# NumberMagic.net
KiCad netlist of a schematic drawn in EAGLE
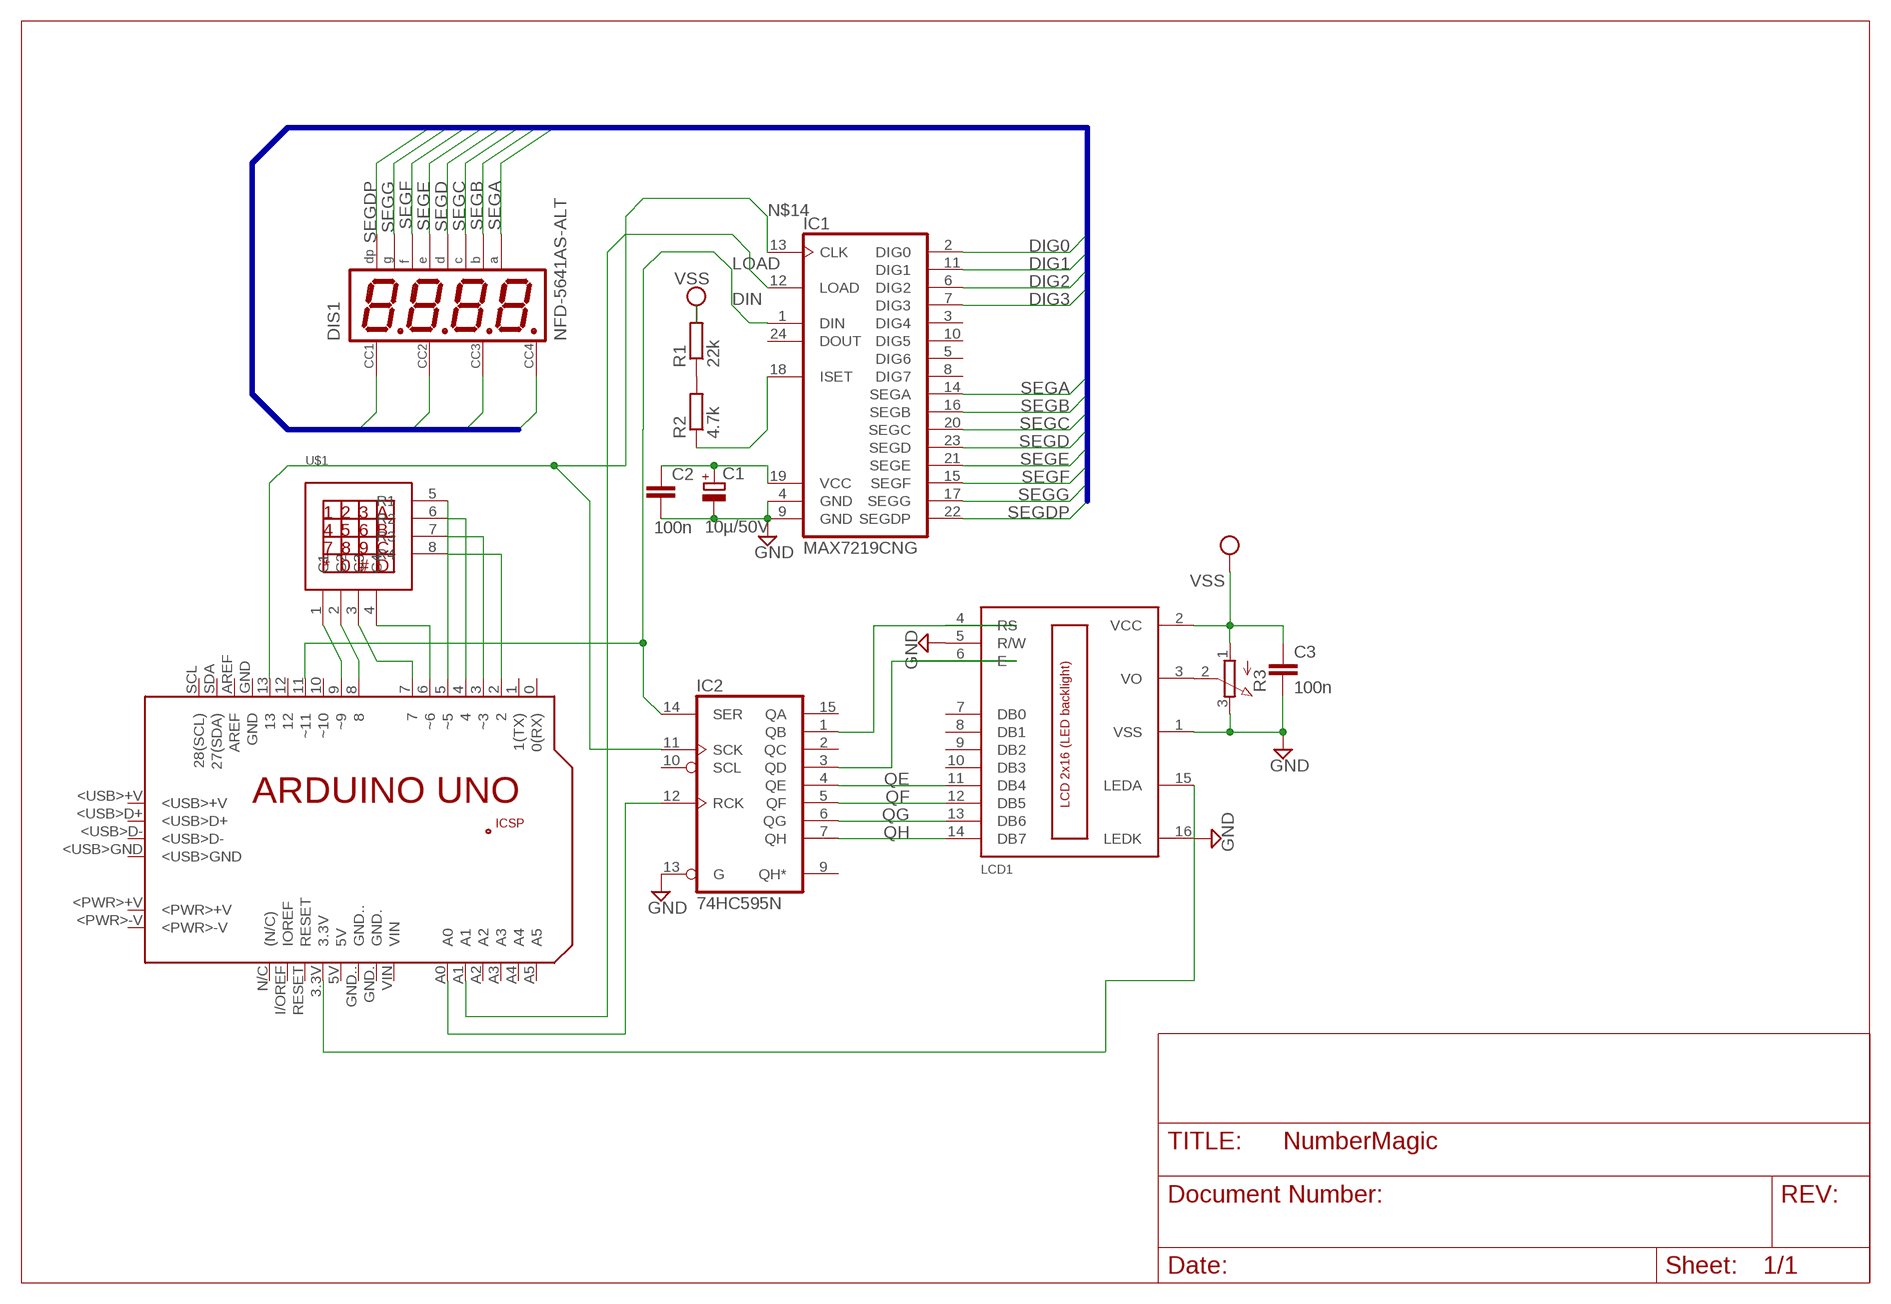
[diagram p0: schematic, sheet 1]

(export (version "E")
  (design (tool "Eeschema 10.0.6"))
  (components
    (comp (ref "C1")
      (value "10µ/50V")
      (footprint "eagle-import:TAP5-50")
      (libsource (lib "eagle-import") (part "CPOL-EUTAP5-50"))
    )
    (comp (ref "C2")
      (value "100n")
      (footprint "eagle-import:C025-024X044")
      (libsource (lib "eagle-import") (part "C-EU025-024X044"))
    )
    (comp (ref "C3")
      (value "100n")
      (footprint "eagle-import:C025-024X044")
      (libsource (lib "eagle-import") (part "C-EU025-024X044"))
    )
    (comp (ref "DIS1")
      (value "NFD-5641AS-ALT")
      (footprint "eagle-import:NFD-5641")
      (libsource (lib "eagle-import") (part "NFD-5641AS-ALT"))
    )
    (comp (ref "IC1")
      (value "MAX7219CNG")
      (footprint "eagle-import:DIL24-3")
      (fields (field (name "MF") "MAXIM"))
      (libsource (lib "eagle-import") (part "MAX7219CNG"))
    )
    (comp (ref "IC2")
      (value "74HC595N")
      (footprint "eagle-import:DIL16")
      (libsource (lib "eagle-import") (part "74595NHC"))
    )
    (comp (ref "LCD1")
      (value "LCD_2X16")
      (footprint "eagle-import:HY-1602F")
      (libsource (lib "eagle-import") (part "LCD_2X16"))
    )
    (comp (ref "PCB1")
      (value "ARDUINO_UNO")
      (footprint "eagle-import:ARDUINO_UNO")
      (libsource (lib "eagle-import") (part "ARDUINO_UNO"))
    )
    (comp (ref "R1")
      (value "22k")
      (footprint "eagle-import:0204_7")
      (libsource (lib "eagle-import") (part "R-EU_0204/7"))
    )
    (comp (ref "R2")
      (value "4.7k")
      (footprint "eagle-import:0204_7")
      (libsource (lib "eagle-import") (part "R-EU_0204/7"))
    )
    (comp (ref "R3")
      (value "3RP/1610N")
      (footprint "eagle-import:3RP_1610N")
      (libsource (lib "eagle-import") (part "3RP/1610N"))
    )
    (comp (ref "U$1")
      (value "KEYPAD4X4")
      (footprint "eagle-import:KEYPAD4X4")
      (libsource (lib "eagle-import") (part "KEYPAD4X4"))
    )
  )
  (nets
    (net (code "1") (name "/DIG0") (class "Default")
      (node (ref "DIS1") (pin "P$12") (pinfunction "P$12_P$12") (pintype "bidirectional"))
      (node (ref "IC1") (pin "2") (pinfunction "DIG0_2") (pintype "output"))
    )
    (net (code "2") (name "/DIG1") (class "Default")
      (node (ref "DIS1") (pin "P$9") (pinfunction "P$9_P$9") (pintype "bidirectional"))
      (node (ref "IC1") (pin "11") (pinfunction "DIG1_11") (pintype "output"))
    )
    (net (code "3") (name "/DIG2") (class "Default")
      (node (ref "DIS1") (pin "P$8") (pinfunction "P$8_P$8") (pintype "bidirectional"))
      (node (ref "IC1") (pin "6") (pinfunction "DIG2_6") (pintype "output"))
    )
    (net (code "4") (name "/DIG3") (class "Default")
      (node (ref "DIS1") (pin "P$6") (pinfunction "P$6_P$6") (pintype "bidirectional"))
      (node (ref "IC1") (pin "7") (pinfunction "DIG3_7") (pintype "output"))
    )
    (net (code "5") (name "/DIN") (class "Default")
      (node (ref "IC1") (pin "1") (pinfunction "DIN_1") (pintype "input"))
      (node (ref "IC2") (pin "14") (pinfunction "SER_14") (pintype "input"))
      (node (ref "PCB1") (pin "11") (pinfunction "~{11}_11") (pintype "bidirectional"))
    )
    (net (code "6") (name "/LOAD") (class "Default")
      (node (ref "IC1") (pin "12") (pinfunction "LOAD_12") (pintype "input"))
      (node (ref "PCB1") (pin "A1") (pinfunction "A1_A1") (pintype "bidirectional"))
    )
    (net (code "7") (name "/N$14") (class "Default")
      (node (ref "IC1") (pin "13") (pinfunction "CLK_13") (pintype "input"))
      (node (ref "IC2") (pin "11") (pinfunction "SCK_11") (pintype "input"))
      (node (ref "PCB1") (pin "13") (pinfunction "13_13") (pintype "bidirectional"))
    )
    (net (code "8") (name "/QE") (class "Default")
      (node (ref "IC2") (pin "4") (pinfunction "QE_4") (pintype "tri_state"))
      (node (ref "LCD1") (pin "11") (pinfunction "DB4_11") (pintype "bidirectional"))
    )
    (net (code "9") (name "/QF") (class "Default")
      (node (ref "IC2") (pin "5") (pinfunction "QF_5") (pintype "tri_state"))
      (node (ref "LCD1") (pin "12") (pinfunction "DB5_12") (pintype "bidirectional"))
    )
    (net (code "10") (name "/QG") (class "Default")
      (node (ref "IC2") (pin "6") (pinfunction "QG_6") (pintype "tri_state"))
      (node (ref "LCD1") (pin "13") (pinfunction "DB6_13") (pintype "bidirectional"))
    )
    (net (code "11") (name "/QH") (class "Default")
      (node (ref "IC2") (pin "7") (pinfunction "QH_7") (pintype "tri_state"))
      (node (ref "LCD1") (pin "14") (pinfunction "DB7_14") (pintype "bidirectional"))
    )
    (net (code "12") (name "/SEGA") (class "Default")
      (node (ref "DIS1") (pin "P$11") (pinfunction "P$11_P$11") (pintype "bidirectional"))
      (node (ref "IC1") (pin "14") (pinfunction "SEGA_14") (pintype "output"))
    )
    (net (code "13") (name "/SEGB") (class "Default")
      (node (ref "DIS1") (pin "P$7") (pinfunction "P$7_P$7") (pintype "bidirectional"))
      (node (ref "IC1") (pin "16") (pinfunction "SEGB_16") (pintype "output"))
    )
    (net (code "14") (name "/SEGC") (class "Default")
      (node (ref "DIS1") (pin "P$4") (pinfunction "P$4_P$4") (pintype "bidirectional"))
      (node (ref "IC1") (pin "20") (pinfunction "SEGC_20") (pintype "output"))
    )
    (net (code "15") (name "/SEGD") (class "Default")
      (node (ref "DIS1") (pin "P$2") (pinfunction "P$2_P$2") (pintype "bidirectional"))
      (node (ref "IC1") (pin "23") (pinfunction "SEGD_23") (pintype "output"))
    )
    (net (code "16") (name "/SEGDP") (class "Default")
      (node (ref "DIS1") (pin "P$3") (pinfunction "P$3_P$3") (pintype "bidirectional"))
      (node (ref "IC1") (pin "22") (pinfunction "SEGDP_22") (pintype "output"))
    )
    (net (code "17") (name "/SEGE") (class "Default")
      (node (ref "DIS1") (pin "P$1") (pinfunction "P$1_P$1") (pintype "bidirectional"))
      (node (ref "IC1") (pin "21") (pinfunction "SEGE_21") (pintype "output"))
    )
    (net (code "18") (name "/SEGF") (class "Default")
      (node (ref "DIS1") (pin "P$10") (pinfunction "P$10_P$10") (pintype "bidirectional"))
      (node (ref "IC1") (pin "15") (pinfunction "SEGF_15") (pintype "output"))
    )
    (net (code "19") (name "/SEGG") (class "Default")
      (node (ref "DIS1") (pin "P$5") (pinfunction "P$5_P$5") (pintype "bidirectional"))
      (node (ref "IC1") (pin "17") (pinfunction "SEGG_17") (pintype "output"))
    )
    (net (code "20") (name "GND") (class "Default")
      (node (ref "C1") (pin "-") (pinfunction "-_-") (pintype "passive"))
      (node (ref "C2") (pin "2") (pinfunction "2_2") (pintype "passive"))
      (node (ref "C3") (pin "2") (pinfunction "2_2") (pintype "passive"))
      (node (ref "IC1") (pin "4") (pinfunction "GND_4") (pintype "power_in"))
      (node (ref "IC1") (pin "9") (pinfunction "GND_9") (pintype "power_in"))
      (node (ref "IC2") (pin "13") (pinfunction "G_13") (pintype "input"))
      (node (ref "LCD1") (pin "1") (pinfunction "VSS_1") (pintype "power_in"))
      (node (ref "LCD1") (pin "16") (pinfunction "LEDK_16") (pintype "passive"))
      (node (ref "LCD1") (pin "5") (pinfunction "R/W_5") (pintype "input"))
      (node (ref "R3") (pin "3") (pinfunction "E_3") (pintype "passive"))
    )
    (net (code "21") (name "Net-(IC1-ISET)") (class "Default")
      (node (ref "IC1") (pin "18") (pinfunction "ISET_18") (pintype "input"))
      (node (ref "R2") (pin "1") (pinfunction "1_1") (pintype "passive"))
    )
    (net (code "22") (name "Net-(IC1-VCC)") (class "Default")
      (node (ref "C1") (pin "+") (pinfunction "+_+") (pintype "passive"))
      (node (ref "C2") (pin "1") (pinfunction "1_1") (pintype "passive"))
      (node (ref "IC1") (pin "19") (pinfunction "VCC_19") (pintype "power_in"))
    )
    (net (code "23") (name "Net-(IC2A-QB)") (class "Default")
      (node (ref "IC2") (pin "1") (pinfunction "QB_1") (pintype "tri_state"))
      (node (ref "LCD1") (pin "4") (pinfunction "RS_4") (pintype "input"))
    )
    (net (code "24") (name "Net-(IC2A-QD)") (class "Default")
      (node (ref "IC2") (pin "3") (pinfunction "QD_3") (pintype "tri_state"))
      (node (ref "LCD1") (pin "6") (pinfunction "E_6") (pintype "input"))
    )
    (net (code "25") (name "Net-(IC2A-RCK)") (class "Default")
      (node (ref "IC2") (pin "12") (pinfunction "RCK_12") (pintype "input"))
      (node (ref "PCB1") (pin "A0") (pinfunction "A0_A0") (pintype "bidirectional"))
    )
    (net (code "26") (name "Net-(LCD1-LEDA)") (class "Default")
      (node (ref "LCD1") (pin "15") (pinfunction "LEDA_15") (pintype "passive"))
      (node (ref "PCB1") (pin "3.3V") (pinfunction "3.3V_3.3V") (pintype "bidirectional"))
    )
    (net (code "27") (name "Net-(LCD1-VO)") (class "Default")
      (node (ref "LCD1") (pin "3") (pinfunction "VO_3") (pintype "input"))
      (node (ref "R3") (pin "2") (pinfunction "S_2") (pintype "passive"))
    )
    (net (code "28") (name "Net-(PCB1-~{3})") (class "Default")
      (node (ref "PCB1") (pin "3") (pinfunction "~{3}_3") (pintype "bidirectional"))
      (node (ref "U$1") (pin "7") (pinfunction "R3_7") (pintype "bidirectional"))
    )
    (net (code "29") (name "Net-(PCB1-~{5})") (class "Default")
      (node (ref "PCB1") (pin "5") (pinfunction "~{5}_5") (pintype "bidirectional"))
      (node (ref "U$1") (pin "5") (pinfunction "R1_5") (pintype "bidirectional"))
    )
    (net (code "30") (name "Net-(PCB1-~{6})") (class "Default")
      (node (ref "PCB1") (pin "6") (pinfunction "~{6}_6") (pintype "bidirectional"))
      (node (ref "U$1") (pin "4") (pinfunction "C4_4") (pintype "bidirectional"))
    )
    (net (code "31") (name "Net-(PCB1-~{9})") (class "Default")
      (node (ref "PCB1") (pin "9") (pinfunction "~{9}_9") (pintype "bidirectional"))
      (node (ref "U$1") (pin "1") (pinfunction "C1_1") (pintype "bidirectional"))
    )
    (net (code "32") (name "Net-(R1-Pad1)") (class "Default")
      (node (ref "R1") (pin "1") (pinfunction "1_1") (pintype "passive"))
      (node (ref "R2") (pin "2") (pinfunction "2_2") (pintype "passive"))
    )
    (net (code "33") (name "Net-(U$1-C2)") (class "Default")
      (node (ref "PCB1") (pin "8") (pinfunction "8_8") (pintype "bidirectional"))
      (node (ref "U$1") (pin "2") (pinfunction "C2_2") (pintype "bidirectional"))
    )
    (net (code "34") (name "Net-(U$1-C3)") (class "Default")
      (node (ref "PCB1") (pin "7") (pinfunction "7_7") (pintype "bidirectional"))
      (node (ref "U$1") (pin "3") (pinfunction "C3_3") (pintype "bidirectional"))
    )
    (net (code "35") (name "Net-(U$1-R2)") (class "Default")
      (node (ref "PCB1") (pin "4") (pinfunction "4_4") (pintype "bidirectional"))
      (node (ref "U$1") (pin "6") (pinfunction "R2_6") (pintype "bidirectional"))
    )
    (net (code "36") (name "Net-(U$1-R4)") (class "Default")
      (node (ref "PCB1") (pin "2") (pinfunction "2_2") (pintype "bidirectional"))
      (node (ref "U$1") (pin "8") (pinfunction "R4_8") (pintype "bidirectional"))
    )
    (net (code "37") (name "VSS") (class "Default")
      (node (ref "C3") (pin "1") (pinfunction "1_1") (pintype "passive"))
      (node (ref "LCD1") (pin "2") (pinfunction "VCC_2") (pintype "power_in"))
      (node (ref "R1") (pin "2") (pinfunction "2_2") (pintype "passive"))
      (node (ref "R3") (pin "1") (pinfunction "A_1") (pintype "passive"))
    )
    (net (code "38") (name "unconnected-(IC1-DIG4-Pad3)") (class "Default")
      (node (ref "IC1") (pin "3") (pinfunction "DIG4_3") (pintype "output"))
    )
    (net (code "39") (name "unconnected-(IC1-DIG5-Pad10)") (class "Default")
      (node (ref "IC1") (pin "10") (pinfunction "DIG5_10") (pintype "output"))
    )
    (net (code "40") (name "unconnected-(IC1-DIG6-Pad5)") (class "Default")
      (node (ref "IC1") (pin "5") (pinfunction "DIG6_5") (pintype "output"))
    )
    (net (code "41") (name "unconnected-(IC1-DIG7-Pad8)") (class "Default")
      (node (ref "IC1") (pin "8") (pinfunction "DIG7_8") (pintype "output"))
    )
    (net (code "42") (name "unconnected-(IC1-DOUT-Pad24)") (class "Default")
      (node (ref "IC1") (pin "24") (pinfunction "DOUT_24") (pintype "output"))
    )
    (net (code "43") (name "unconnected-(IC2A-QA-Pad15)") (class "Default")
      (node (ref "IC2") (pin "15") (pinfunction "QA_15") (pintype "tri_state"))
    )
    (net (code "44") (name "unconnected-(IC2A-QC-Pad2)") (class "Default")
      (node (ref "IC2") (pin "2") (pinfunction "QC_2") (pintype "tri_state"))
    )
    (net (code "45") (name "unconnected-(IC2A-QH*-Pad9)") (class "Default")
      (node (ref "IC2") (pin "9") (pinfunction "QH*_9") (pintype "tri_state"))
    )
    (net (code "46") (name "unconnected-(IC2A-SCL-Pad10)") (class "Default")
      (node (ref "IC2") (pin "10") (pinfunction "SCL_10") (pintype "input"))
    )
    (net (code "47") (name "unconnected-(LCD1-DB0-Pad7)") (class "Default")
      (node (ref "LCD1") (pin "7") (pinfunction "DB0_7") (pintype "bidirectional"))
    )
    (net (code "48") (name "unconnected-(LCD1-DB1-Pad8)") (class "Default")
      (node (ref "LCD1") (pin "8") (pinfunction "DB1_8") (pintype "bidirectional"))
    )
    (net (code "49") (name "unconnected-(LCD1-DB2-Pad9)") (class "Default")
      (node (ref "LCD1") (pin "9") (pinfunction "DB2_9") (pintype "bidirectional"))
    )
    (net (code "50") (name "unconnected-(LCD1-DB3-Pad10)") (class "Default")
      (node (ref "LCD1") (pin "10") (pinfunction "DB3_10") (pintype "bidirectional"))
    )
    (net (code "51") (name "unconnected-(PCB1-(N{slash}C)-PadN{slash}C)") (class "Default")
      (node (ref "PCB1") (pin "N/C") (pinfunction "(N/C)_N/C") (pintype "bidirectional"))
    )
    (net (code "52") (name "unconnected-(PCB1-0(RX)-Pad0)") (class "Default")
      (node (ref "PCB1") (pin "0") (pinfunction "0(RX)_0") (pintype "bidirectional"))
    )
    (net (code "53") (name "unconnected-(PCB1-1(TX)-Pad1)") (class "Default")
      (node (ref "PCB1") (pin "1") (pinfunction "1(TX)_1") (pintype "bidirectional"))
    )
    (net (code "54") (name "unconnected-(PCB1-27(SDA)-PadSDA)") (class "Default")
      (node (ref "PCB1") (pin "SDA") (pinfunction "27(SDA)_SDA") (pintype "bidirectional"))
    )
    (net (code "55") (name "unconnected-(PCB1-28(SCL)-PadSCL)") (class "Default")
      (node (ref "PCB1") (pin "SCL") (pinfunction "28(SCL)_SCL") (pintype "bidirectional"))
    )
    (net (code "56") (name "unconnected-(PCB1-IOREF-PadI{slash}OREF)") (class "Default")
      (node (ref "PCB1") (pin "I/OREF") (pinfunction "IOREF_I/OREF") (pintype "bidirectional"))
    )
    (net (code "57") (name "unconnected-(PCB1-Pad+5V)") (class "Default")
      (node (ref "PCB1") (pin "+5V") (pinfunction "+5V_+5V") (pintype "bidirectional"))
    )
    (net (code "58") (name "unconnected-(PCB1-Pad5V)") (class "Default")
      (node (ref "PCB1") (pin "5V") (pinfunction "5V_5V") (pintype "bidirectional"))
    )
    (net (code "59") (name "unconnected-(PCB1-Pad12)") (class "Default")
      (node (ref "PCB1") (pin "12") (pinfunction "12_12") (pintype "bidirectional"))
    )
    (net (code "60") (name "unconnected-(PCB1-Pad<PWR>+V)") (class "Default")
      (node (ref "PCB1") (pin "<PWR>+V") (pinfunction "<PWR>+V_<PWR>+V") (pintype "bidirectional"))
    )
    (net (code "61") (name "unconnected-(PCB1-Pad<PWR>-V)") (class "Default")
      (node (ref "PCB1") (pin "<PWR>-V") (pinfunction "<PWR>-V_<PWR>-V") (pintype "bidirectional"))
    )
    (net (code "62") (name "unconnected-(PCB1-Pad<USB>+V)") (class "Default")
      (node (ref "PCB1") (pin "<USB>+V") (pinfunction "<USB>+V_<USB>+V") (pintype "bidirectional"))
    )
    (net (code "63") (name "unconnected-(PCB1-Pad<USB>D+)") (class "Default")
      (node (ref "PCB1") (pin "<USB>D+") (pinfunction "<USB>D+_<USB>D+") (pintype "bidirectional"))
    )
    (net (code "64") (name "unconnected-(PCB1-Pad<USB>D-)") (class "Default")
      (node (ref "PCB1") (pin "<USB>D-") (pinfunction "<USB>D-_<USB>D-") (pintype "bidirectional"))
    )
    (net (code "65") (name "unconnected-(PCB1-Pad<USB>GND)") (class "Default")
      (node (ref "PCB1") (pin "<USB>GND") (pinfunction "<USB>GND_<USB>GND") (pintype "bidirectional"))
    )
    (net (code "66") (name "unconnected-(PCB1-PadA2)") (class "Default")
      (node (ref "PCB1") (pin "A2") (pinfunction "A2_A2") (pintype "bidirectional"))
    )
    (net (code "67") (name "unconnected-(PCB1-PadA3)") (class "Default")
      (node (ref "PCB1") (pin "A3") (pinfunction "A3_A3") (pintype "bidirectional"))
    )
    (net (code "68") (name "unconnected-(PCB1-PadA4)") (class "Default")
      (node (ref "PCB1") (pin "A4") (pinfunction "A4_A4") (pintype "bidirectional"))
    )
    (net (code "69") (name "unconnected-(PCB1-PadA5)") (class "Default")
      (node (ref "PCB1") (pin "A5") (pinfunction "A5_A5") (pintype "bidirectional"))
    )
    (net (code "70") (name "unconnected-(PCB1-PadAREF)") (class "Default")
      (node (ref "PCB1") (pin "AREF") (pinfunction "AREF_AREF") (pintype "bidirectional"))
    )
    (net (code "71") (name "unconnected-(PCB1-PadGND)") (class "Default")
      (node (ref "PCB1") (pin "GND") (pinfunction "GND_GND") (pintype "bidirectional"))
    )
    (net (code "72") (name "unconnected-(PCB1-PadGND.)") (class "Default")
      (node (ref "PCB1") (pin "GND.") (pinfunction "GND._GND.") (pintype "bidirectional"))
    )
    (net (code "73") (name "unconnected-(PCB1-PadGND..)") (class "Default")
      (node (ref "PCB1") (pin "GND..") (pinfunction "GND.._GND..") (pintype "bidirectional"))
    )
    (net (code "74") (name "unconnected-(PCB1-PadGND_)") (class "Default")
      (node (ref "PCB1") (pin "GND_") (pinfunction "GND__GND_") (pintype "bidirectional"))
    )
    (net (code "75") (name "unconnected-(PCB1-PadMISO)") (class "Default")
      (node (ref "PCB1") (pin "MISO") (pinfunction "MISO_MISO") (pintype "bidirectional"))
    )
    (net (code "76") (name "unconnected-(PCB1-PadMOSI)") (class "Default")
      (node (ref "PCB1") (pin "MOSI") (pinfunction "MOSI_MOSI") (pintype "bidirectional"))
    )
    (net (code "77") (name "unconnected-(PCB1-PadRESET)") (class "Default")
      (node (ref "PCB1") (pin "RESET") (pinfunction "RESET_RESET") (pintype "bidirectional"))
    )
    (net (code "78") (name "unconnected-(PCB1-PadRESET.)") (class "Default")
      (node (ref "PCB1") (pin "RESET.") (pinfunction "RESET._RESET.") (pintype "bidirectional"))
    )
    (net (code "79") (name "unconnected-(PCB1-PadSCK)") (class "Default")
      (node (ref "PCB1") (pin "SCK") (pinfunction "SCK_SCK") (pintype "bidirectional"))
    )
    (net (code "80") (name "unconnected-(PCB1-PadVIN)") (class "Default")
      (node (ref "PCB1") (pin "VIN") (pinfunction "VIN_VIN") (pintype "bidirectional"))
    )
    (net (code "81") (name "unconnected-(PCB1-~{10}-Pad10)") (class "Default")
      (node (ref "PCB1") (pin "10") (pinfunction "~{10}_10") (pintype "bidirectional"))
    )
  )
)
